# Dac_Reference.net
KiCad netlist of a schematic drawn in Altium Designer
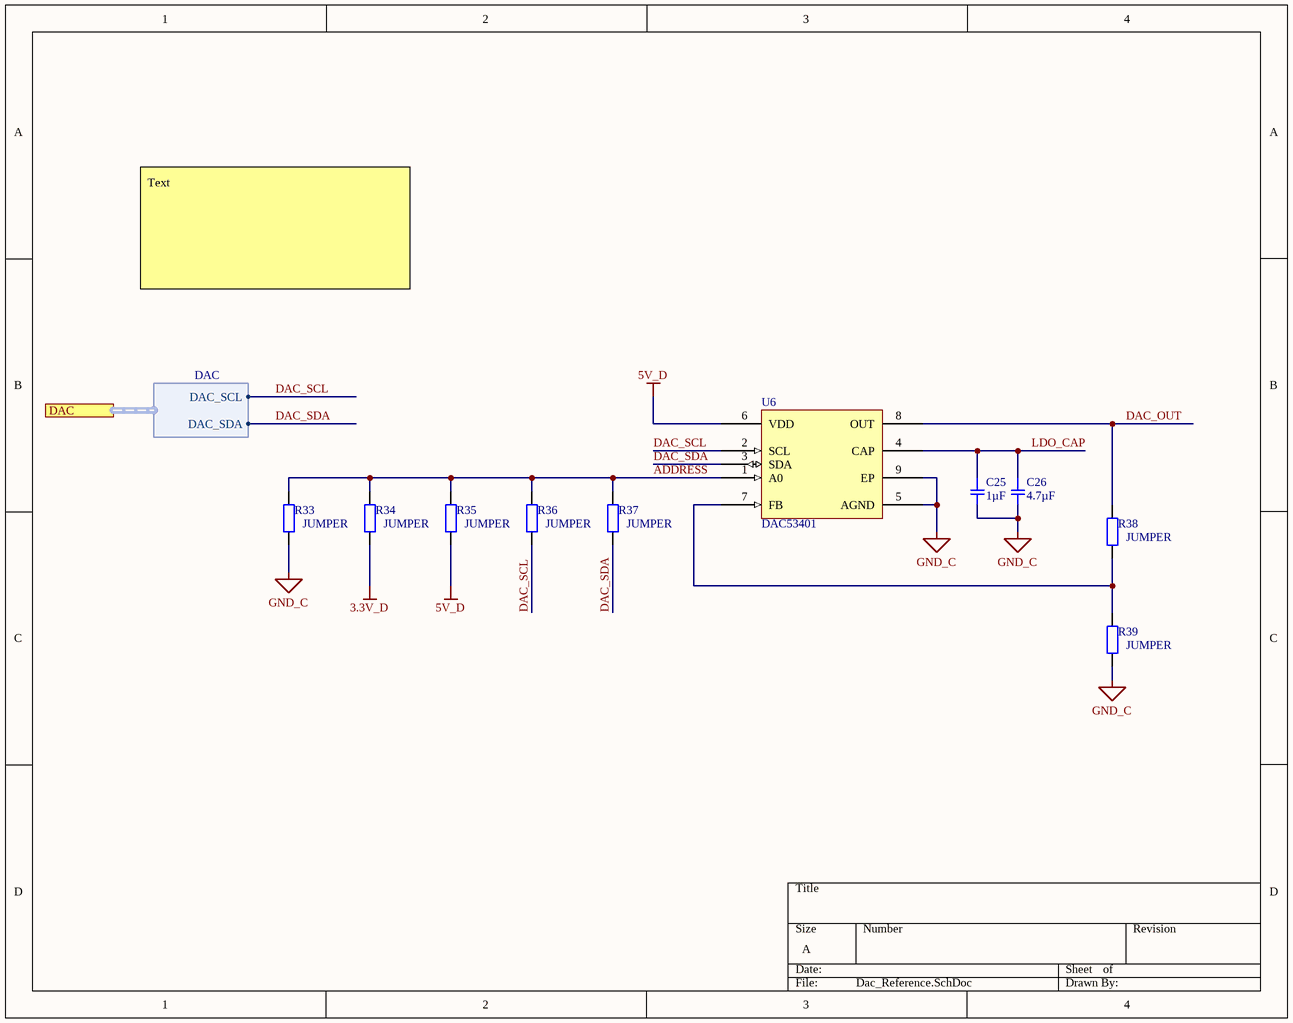
[diagram p0: Dac_Reference.SchDoc]

(export (version "E")
  (design (tool "Eeschema 10.0.6"))
  (components
    (comp (ref "C25")
      (value "1µF")
      (footprint "SMD-0805C")
      (description "CAP CER 1UF 16V X7R 0805")
      (fields
        (field (name "DIGI-KEY PART NUMBER") "490-5800-1-ND")
        (field (name "PART NUMBER") "GCJ219R71C105KA01D")
      )
      (libsource (lib "capacitor_murata_0805") (part "GCJ219R71C105KA01D"))
    )
    (comp (ref "C26")
      (value "4.7µF")
      (footprint "SMD-1206C")
      (description "CAP CER 4.7UF 25V X7R 1206")
      (fields
        (field (name "DIGI-KEY PART NUMBER") "490-5808-1-ND")
        (field (name "PART NUMBER") "GCJ31CR71E475KA12L")
      )
      (libsource (lib "capacitor_murata_1206") (part "GCJ31CR71E475KA12L"))
    )
    (comp (ref "R33")
      (value "JUMPER")
      (footprint "WRIS-KSKE_0603_H=0.45mm")
      (description "WRIS-KSKE Thick Film Resistors, size 0603, 10Ohm, +/-1%, 0.25W")
      (fields (field (name "PART NUMBER") "560050316012") (field (name "PUBLISHER") "Wurth Elektronik"))
      (libsource (lib "Altium_WRIS-KSKE_rev19a") (part "560050316012"))
    )
    (comp (ref "R34")
      (value "JUMPER")
      (footprint "WRIS-KSKE_0603_H=0.45mm")
      (description "WRIS-KSKE Thick Film Resistors, size 0603, 10Ohm, +/-1%, 0.25W")
      (fields (field (name "PART NUMBER") "560050316012") (field (name "PUBLISHER") "Wurth Elektronik"))
      (libsource (lib "Altium_WRIS-KSKE_rev19a") (part "560050316012"))
    )
    (comp (ref "R35")
      (value "JUMPER")
      (footprint "WRIS-KSKE_0603_H=0.45mm")
      (description "WRIS-KSKE Thick Film Resistors, size 0603, 10Ohm, +/-1%, 0.25W")
      (fields (field (name "PART NUMBER") "560050316012") (field (name "PUBLISHER") "Wurth Elektronik"))
      (libsource (lib "Altium_WRIS-KSKE_rev19a") (part "560050316012"))
    )
    (comp (ref "R36")
      (value "JUMPER")
      (footprint "WRIS-KSKE_0603_H=0.45mm")
      (description "WRIS-KSKE Thick Film Resistors, size 0603, 10Ohm, +/-1%, 0.25W")
      (fields (field (name "PART NUMBER") "560050316012") (field (name "PUBLISHER") "Wurth Elektronik"))
      (libsource (lib "Altium_WRIS-KSKE_rev19a") (part "560050316012"))
    )
    (comp (ref "R37")
      (value "JUMPER")
      (footprint "WRIS-KSKE_0603_H=0.45mm")
      (description "WRIS-KSKE Thick Film Resistors, size 0603, 10Ohm, +/-1%, 0.25W")
      (fields (field (name "PART NUMBER") "560050316012") (field (name "PUBLISHER") "Wurth Elektronik"))
      (libsource (lib "Altium_WRIS-KSKE_rev19a") (part "560050316012"))
    )
    (comp (ref "R38")
      (value "JUMPER")
      (footprint "WRIS-KSKE_0603_H=0.45mm")
      (description "WRIS-KSKE Thick Film Resistors, size 0603, 10Ohm, +/-1%, 0.25W")
      (fields (field (name "PART NUMBER") "560050316012") (field (name "PUBLISHER") "Wurth Elektronik"))
      (libsource (lib "Altium_WRIS-KSKE_rev19a") (part "560050316012"))
    )
    (comp (ref "R39")
      (value "JUMPER")
      (footprint "WRIS-KSKE_0603_H=0.45mm")
      (description "WRIS-KSKE Thick Film Resistors, size 0603, 10Ohm, +/-1%, 0.25W")
      (fields (field (name "PART NUMBER") "560050316012") (field (name "PUBLISHER") "Wurth Elektronik"))
      (libsource (lib "Altium_WRIS-KSKE_rev19a") (part "560050316012"))
    )
    (comp (ref "U6")
      (value "DAC53401")
      (footprint "SON50P200X80_HS-9N")
      (libsource (lib "Edge_Card_Ucc28951") (part "CMP-0000-53401-1"))
    )
  )
  (nets
    (net (code "2") (name "/ADDRESS") (class "Default")
      (node (ref "R33") (pin "2") (pinfunction "2_2") (pintype "passive"))
      (node (ref "R34") (pin "2") (pinfunction "2_2") (pintype "passive"))
      (node (ref "R35") (pin "2") (pinfunction "2_2") (pintype "passive"))
      (node (ref "R36") (pin "2") (pinfunction "2_2") (pintype "passive"))
      (node (ref "R37") (pin "2") (pinfunction "2_2") (pintype "passive"))
      (node (ref "U6") (pin "1") (pinfunction "A0_1") (pintype "input"))
    )
    (net (code "3") (name "/DAC_OUT") (class "Default")
      (node (ref "R38") (pin "2") (pinfunction "2_2") (pintype "passive"))
      (node (ref "U6") (pin "8") (pinfunction "OUT_8") (pintype "passive"))
    )
    (net (code "4") (name "/DAC_SCL") (class "Default")
      (node (ref "R36") (pin "1") (pinfunction "1_1") (pintype "passive"))
      (node (ref "U6") (pin "2") (pinfunction "SCL_2") (pintype "input"))
    )
    (net (code "5") (name "/DAC_SDA") (class "Default")
      (node (ref "R37") (pin "1") (pinfunction "1_1") (pintype "passive"))
      (node (ref "U6") (pin "3") (pinfunction "SDA_3") (pintype "bidirectional"))
    )
    (net (code "6") (name "/LDO_CAP") (class "Default")
      (node (ref "C25") (pin "1") (pinfunction "1_1") (pintype "passive"))
      (node (ref "C26") (pin "1") (pinfunction "1_1") (pintype "passive"))
      (node (ref "U6") (pin "4") (pinfunction "CAP_4") (pintype "passive"))
    )
    (net (code "8") (name "3.3V_D") (class "Default")
      (node (ref "R34") (pin "1") (pinfunction "1_1") (pintype "passive"))
    )
    (net (code "9") (name "5V_D") (class "Default")
      (node (ref "R35") (pin "1") (pinfunction "1_1") (pintype "passive"))
      (node (ref "U6") (pin "6") (pinfunction "VDD_6") (pintype "passive"))
    )
    (net (code "10") (name "GND_C") (class "Default")
      (node (ref "C25") (pin "2") (pinfunction "2_2") (pintype "passive"))
      (node (ref "C26") (pin "2") (pinfunction "2_2") (pintype "passive"))
      (node (ref "R33") (pin "1") (pinfunction "1_1") (pintype "passive"))
      (node (ref "R39") (pin "1") (pinfunction "1_1") (pintype "passive"))
      (node (ref "U6") (pin "5") (pinfunction "AGND_5") (pintype "passive"))
      (node (ref "U6") (pin "9") (pinfunction "EP_9") (pintype "passive"))
    )
    (net (code "11") (name "Net-(U6-FB)") (class "Default")
      (node (ref "R38") (pin "1") (pinfunction "1_1") (pintype "passive"))
      (node (ref "R39") (pin "2") (pinfunction "2_2") (pintype "passive"))
      (node (ref "U6") (pin "7") (pinfunction "FB_7") (pintype "input"))
    )
  )
)
